# Sony_PSP_USB-C.net
KiCad netlist of a schematic drawn in EAGLE
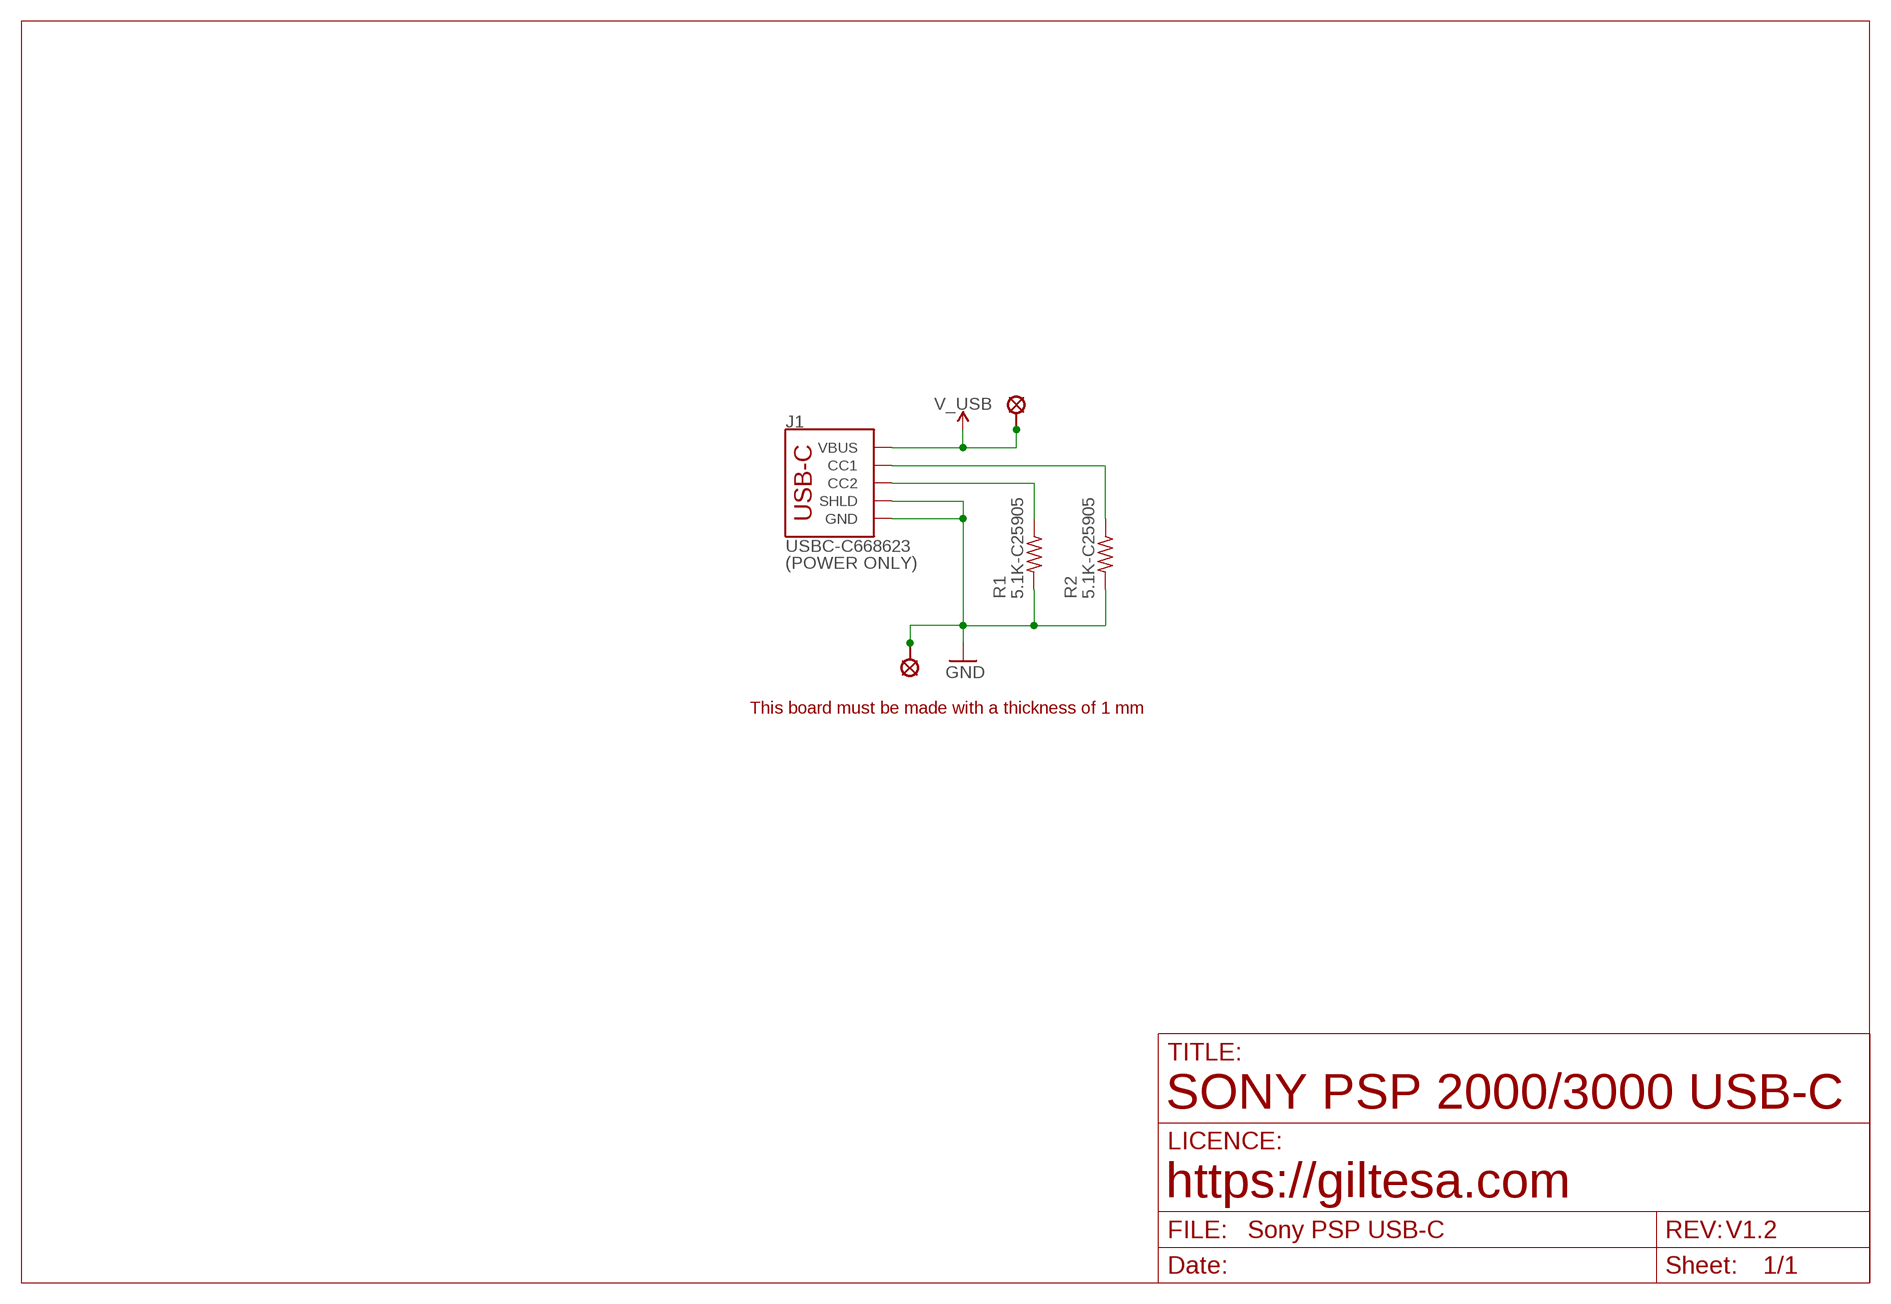
[diagram p0: schematic, sheet 1]

(export (version "E")
  (design (tool "Eeschema 10.0.6"))
  (components
    (comp (ref "J1")
      (value "USBC-C668623")
      (footprint "eagle-import:USB-C_6P")
      (libsource (lib "eagle-import") (part "USB-CPOWER"))
    )
    (comp (ref "R1")
      (value "5.1K-C25905")
      (footprint "eagle-import:R0402")
      (libsource (lib "eagle-import") (part "R0402"))
    )
    (comp (ref "R2")
      (value "5.1K-C25905")
      (footprint "eagle-import:R0402")
      (libsource (lib "eagle-import") (part "R0402"))
    )
    (comp (ref "U$1")
      (value "SOLDER_PAD_N3DS")
      (footprint "eagle-import:N3DS_TPAD")
      (libsource (lib "eagle-import") (part "SOLDER_PAD_N3DS"))
    )
    (comp (ref "U$2")
      (value "SOLDER_PAD_N3DS")
      (footprint "eagle-import:N3DS_TPAD")
      (libsource (lib "eagle-import") (part "SOLDER_PAD_N3DS"))
    )
    (comp (ref "U$3")
      (value "SOLDER_PAD_N3DS")
      (footprint "eagle-import:N3DS_TPAD")
      (libsource (lib "eagle-import") (part "SOLDER_PAD_N3DS"))
    )
    (comp (ref "U$4")
      (value "SOLDER_PAD_N3DS")
      (footprint "eagle-import:N3DS_TPAD")
      (libsource (lib "eagle-import") (part "SOLDER_PAD_N3DS"))
    )
  )
  (nets
    (net (code "1") (name "GND") (class "Default")
      (node (ref "J1") (pin "GND1") (pinfunction "GND_GND1") (pintype "bidirectional"))
      (node (ref "J1") (pin "GND2") (pinfunction "GND_GND2") (pintype "bidirectional"))
      (node (ref "J1") (pin "SHLD1") (pinfunction "SHLD_SHLD1") (pintype "bidirectional"))
      (node (ref "J1") (pin "SHLD2") (pinfunction "SHLD_SHLD2") (pintype "bidirectional"))
      (node (ref "J1") (pin "SHLD3") (pinfunction "SHLD_SHLD3") (pintype "bidirectional"))
      (node (ref "J1") (pin "SHLD4") (pinfunction "SHLD_SHLD4") (pintype "bidirectional"))
      (node (ref "J1") (pin "SHLD5") (pinfunction "SHLD_SHLD5") (pintype "bidirectional"))
      (node (ref "J1") (pin "SHLD6") (pinfunction "SHLD_SHLD6") (pintype "bidirectional"))
      (node (ref "J1") (pin "SHLD7") (pinfunction "SHLD_SHLD7") (pintype "bidirectional"))
      (node (ref "J1") (pin "SHLD8") (pinfunction "SHLD_SHLD8") (pintype "bidirectional"))
      (node (ref "R1") (pin "2") (pinfunction "2_2") (pintype "passive"))
      (node (ref "R2") (pin "2") (pinfunction "2_2") (pintype "passive"))
      (node (ref "U$1") (pin "1") (pinfunction "P$1_1") (pintype "bidirectional"))
      (node (ref "U$4") (pin "1") (pinfunction "P$1_1") (pintype "bidirectional"))
    )
    (net (code "2") (name "Net-(J1-CC1)") (class "Default")
      (node (ref "J1") (pin "A5") (pinfunction "CC1_A5") (pintype "bidirectional"))
      (node (ref "R2") (pin "1") (pinfunction "1_1") (pintype "passive"))
    )
    (net (code "3") (name "Net-(J1-CC2)") (class "Default")
      (node (ref "J1") (pin "B5") (pinfunction "CC2_B5") (pintype "bidirectional"))
      (node (ref "R1") (pin "1") (pinfunction "1_1") (pintype "passive"))
    )
    (net (code "4") (name "V_USB") (class "Default")
      (node (ref "J1") (pin "VBUS1") (pinfunction "VBUS_VBUS1") (pintype "bidirectional"))
      (node (ref "J1") (pin "VBUS2") (pinfunction "VBUS_VBUS2") (pintype "bidirectional"))
      (node (ref "U$2") (pin "1") (pinfunction "P$1_1") (pintype "bidirectional"))
      (node (ref "U$3") (pin "1") (pinfunction "P$1_1") (pintype "bidirectional"))
    )
  )
)
